# MedioPuente.net
KiCad netlist of a schematic drawn in Altium Designer
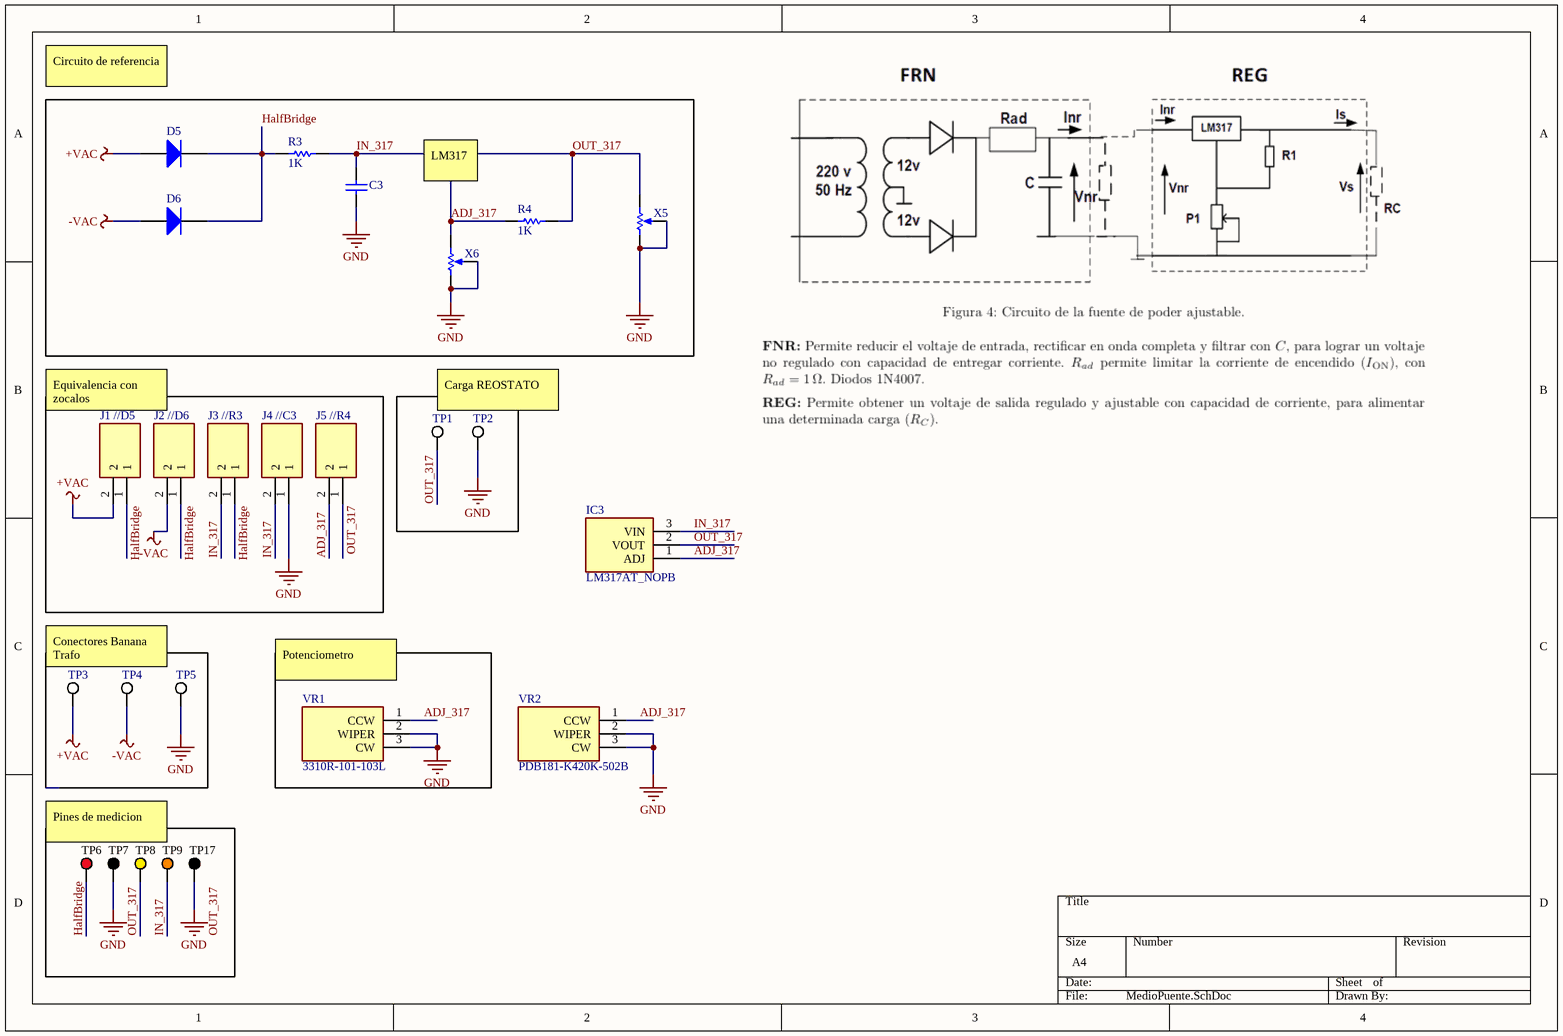
[diagram p0: MedioPuente.SchDoc]

(export (version "E")
  (design (tool "Eeschema 10.0.6"))
  (components
    (comp (ref "C3") (value "Capacitor") (libsource (lib "Simulation Generic Components") (part "Capacitor")))
    (comp (ref "D5") (value "Diode") (libsource (lib "Simulation Generic Components") (part "Diode")))
    (comp (ref "D6") (value "Diode") (libsource (lib "Simulation Generic Components") (part "Diode")))
    (comp (ref "IC3")
      (value "LM317AT_NOPB")
      (footprint "TO254P470X1028X1955-3P")
      (description "Integrated Circuit")
      (fields
        (field (name "MANUFACTURER_PART_NUMBER") "LM317AT/NOPB")
        (field (name "MOUSER PART NUMBER") "926-LM317AT/NOPB")
      )
      (libsource (lib "LM317") (part "LM317AT_NOPB"))
    )
    (comp (ref "J1")
      (value "D01-9970242")
      (footprint "D019970242")
      (description "IC Socket: 2 Pos Receptacle SIL Straight THT Strip")
      (fields (field (name "MOUSER PART NUMBER") "855-D01-9970242"))
      (libsource (lib "Zocalo_2pines") (part "D01-9970242"))
    )
    (comp (ref "J2")
      (value "D01-9970242")
      (footprint "D019970242")
      (description "IC Socket: 2 Pos Receptacle SIL Straight THT Strip")
      (fields (field (name "MOUSER PART NUMBER") "855-D01-9970242"))
      (libsource (lib "Zocalo_2pines") (part "D01-9970242"))
    )
    (comp (ref "J3")
      (value "D01-9970242")
      (footprint "D019970242")
      (description "IC Socket: 2 Pos Receptacle SIL Straight THT Strip")
      (fields (field (name "MOUSER PART NUMBER") "855-D01-9970242"))
      (libsource (lib "Zocalo_2pines") (part "D01-9970242"))
    )
    (comp (ref "J4")
      (value "D01-9970242")
      (footprint "D019970242")
      (description "IC Socket: 2 Pos Receptacle SIL Straight THT Strip")
      (fields (field (name "MOUSER PART NUMBER") "855-D01-9970242"))
      (libsource (lib "Zocalo_2pines") (part "D01-9970242"))
    )
    (comp (ref "J5")
      (value "D01-9970242")
      (footprint "D019970242")
      (description "IC Socket: 2 Pos Receptacle SIL Straight THT Strip")
      (fields (field (name "MOUSER PART NUMBER") "855-D01-9970242"))
      (libsource (lib "Zocalo_2pines") (part "D01-9970242"))
    )
    (comp (ref "R3")
      (value "1K")
      (description "Resistor")
      (libsource (lib "Simulation Generic Components") (part "Resistor"))
    )
    (comp (ref "R4")
      (value "1K")
      (description "Resistor")
      (libsource (lib "Simulation Generic Components") (part "Resistor"))
    )
    (comp (ref "TP1")
      (value "575-4")
      (footprint "KSTN-575-4")
      (description "Banana Jack, Non-Insulated, 1-Pin THD, RoHS, Bulk")
      (fields (field (name "MANUFACTURER") "Keystone-Electronics"))
      (libsource (lib "Altium Content Vault") (part "TESTPOINT_WHITE"))
    )
    (comp (ref "TP2")
      (value "575-4")
      (footprint "KSTN-575-4")
      (description "Banana Jack, Non-Insulated, 1-Pin THD, RoHS, Bulk")
      (fields (field (name "MANUFACTURER") "Keystone-Electronics"))
      (libsource (lib "Altium Content Vault") (part "TESTPOINT_WHITE"))
    )
    (comp (ref "TP3")
      (value "575-4")
      (footprint "KSTN-575-4")
      (description "Banana Jack, Non-Insulated, 1-Pin THD, RoHS, Bulk")
      (fields (field (name "MANUFACTURER") "Keystone-Electronics"))
      (libsource (lib "Altium Content Vault") (part "TESTPOINT_WHITE"))
    )
    (comp (ref "TP4")
      (value "575-4")
      (footprint "KSTN-575-4")
      (description "Banana Jack, Non-Insulated, 1-Pin THD, RoHS, Bulk")
      (fields (field (name "MANUFACTURER") "Keystone-Electronics"))
      (libsource (lib "Altium Content Vault") (part "TESTPOINT_WHITE"))
    )
    (comp (ref "TP5")
      (value "575-4")
      (footprint "KSTN-575-4")
      (description "Banana Jack, Non-Insulated, 1-Pin THD, RoHS, Bulk")
      (fields (field (name "MANUFACTURER") "Keystone-Electronics"))
      (libsource (lib "Altium Content Vault") (part "TESTPOINT_WHITE"))
    )
    (comp (ref "TP6")
      (value "5010")
      (footprint "KSTN-5010_V")
      (description "Test Point, Red, Through Hole, RoHS, Bulk")
      (fields (field (name "MANUFACTURER") "Keystone"))
      (libsource (lib "Altium Content Vault") (part "TESTPOINT_RED"))
    )
    (comp (ref "TP7")
      (value "5011")
      (footprint "KSTN-5011_V")
      (description "Test Point, Black, Through Hole, RoHS, Bulk")
      (fields (field (name "MANUFACTURER") "Keystone"))
      (libsource (lib "Altium Content Vault") (part "TESTPOINT_BLACK"))
    )
    (comp (ref "TP8")
      (value "5014")
      (footprint "KSTN-5014_V")
      (description "Test Point, Yellow, Through Hole, RoHS, Bulk")
      (fields (field (name "MANUFACTURER") "Keystone"))
      (libsource (lib "Altium Content Vault") (part "TESTPOINT_YELLOW"))
    )
    (comp (ref "TP9")
      (value "5013")
      (footprint "KSTN-5013_V")
      (description "Test Point, Orange, Through Hole, RoHS, Bulk")
      (fields (field (name "MANUFACTURER") "Keystone"))
      (libsource (lib "Altium Content Vault") (part "TESTPOINT_ORANGE"))
    )
    (comp (ref "TP17")
      (value "5011")
      (footprint "KSTN-5011_V")
      (description "Test Point, Black, Through Hole, RoHS, Bulk")
      (fields (field (name "MANUFACTURER") "Keystone"))
      (libsource (lib "Altium Content Vault") (part "TESTPOINT_BLACK"))
    )
    (comp (ref "VR1")
      (value "3310R-101-103L")
      (footprint "3310R125103L")
      (description "Variable Resistor")
      (fields (field (name "MOUSER PART NUMBER") "652-3310R-101-103L"))
      (libsource (lib "Potenciometro") (part "3310R-101-103L"))
    )
    (comp (ref "VR2")
      (value "PDB181-K420K-502B")
      (footprint "Potenciometro5K:PDB181K220K104B")
      (description "Variable Resistor")
      (fields (field (name "MOUSER PART NUMBER") "652-PDB181-K420K502B"))
      (libsource (lib "Potenciometro5K") (part "PDB181-K420K-502B"))
    )
    (comp (ref "X5")
      (value "Potentiometer")
      (libsource (lib "Simulation Generic Components") (part "Potentiometer"))
    )
    (comp (ref "X6")
      (value "Potentiometer")
      (libsource (lib "Simulation Generic Components") (part "Potentiometer"))
    )
  )
  (nets
    (net (code "1") (name "+VAC") (class "Default")
      (node (ref "D5") (pin "1") (pinfunction "A_1") (pintype "passive"))
      (node (ref "J1") (pin "2") (pinfunction "2_2") (pintype "passive"))
      (node (ref "TP3") (pin "1") (pinfunction "1_1") (pintype "passive"))
    )
    (net (code "2") (name "-VAC") (class "Default")
      (node (ref "D6") (pin "1") (pinfunction "A_1") (pintype "passive"))
      (node (ref "J2") (pin "2") (pinfunction "2_2") (pintype "passive"))
      (node (ref "TP4") (pin "1") (pinfunction "1_1") (pintype "passive"))
    )
    (net (code "3") (name "/ADJ_317") (class "Default")
      (node (ref "IC3") (pin "1") (pinfunction "ADJ_1") (pintype "passive"))
      (node (ref "J5") (pin "2") (pinfunction "2_2") (pintype "passive"))
      (node (ref "R4") (pin "1") (pinfunction "1_1") (pintype "passive"))
      (node (ref "VR1") (pin "1") (pinfunction "CCW_1") (pintype "passive"))
      (node (ref "VR2") (pin "1") (pinfunction "CCW_1") (pintype "passive"))
      (node (ref "X6") (pin "2") (pinfunction "BOT_2") (pintype "passive"))
    )
    (net (code "4") (name "/HalfBridge") (class "Default")
      (node (ref "D5") (pin "2") (pinfunction "K_2") (pintype "passive"))
      (node (ref "D6") (pin "2") (pinfunction "K_2") (pintype "passive"))
      (node (ref "J1") (pin "1") (pinfunction "1_1") (pintype "passive"))
      (node (ref "J2") (pin "1") (pinfunction "1_1") (pintype "passive"))
      (node (ref "J3") (pin "1") (pinfunction "1_1") (pintype "passive"))
      (node (ref "R3") (pin "1") (pinfunction "1_1") (pintype "passive"))
      (node (ref "TP6") (pin "1") (pinfunction "1_1") (pintype "passive"))
    )
    (net (code "5") (name "/IN_317") (class "Default")
      (node (ref "C3") (pin "2") (pinfunction "2_2") (pintype "passive"))
      (node (ref "IC3") (pin "3") (pinfunction "VIN_3") (pintype "passive"))
      (node (ref "J3") (pin "2") (pinfunction "2_2") (pintype "passive"))
      (node (ref "J4") (pin "2") (pinfunction "2_2") (pintype "passive"))
      (node (ref "R3") (pin "2") (pinfunction "2_2") (pintype "passive"))
      (node (ref "TP9") (pin "1") (pinfunction "1_1") (pintype "passive"))
    )
    (net (code "6") (name "/OUT_317") (class "Default")
      (node (ref "IC3") (pin "2") (pinfunction "VOUT_2") (pintype "passive"))
      (node (ref "J5") (pin "1") (pinfunction "1_1") (pintype "passive"))
      (node (ref "R4") (pin "2") (pinfunction "2_2") (pintype "passive"))
      (node (ref "TP1") (pin "1") (pinfunction "1_1") (pintype "passive"))
      (node (ref "TP8") (pin "1") (pinfunction "1_1") (pintype "passive"))
      (node (ref "X5") (pin "2") (pinfunction "BOT_2") (pintype "passive"))
    )
    (net (code "7") (name "GND") (class "Default")
      (node (ref "C3") (pin "1") (pinfunction "1_1") (pintype "passive"))
      (node (ref "J4") (pin "1") (pinfunction "1_1") (pintype "passive"))
      (node (ref "TP17") (pin "1") (pinfunction "1_1") (pintype "passive"))
      (node (ref "TP2") (pin "1") (pinfunction "1_1") (pintype "passive"))
      (node (ref "TP5") (pin "1") (pinfunction "1_1") (pintype "passive"))
      (node (ref "TP7") (pin "1") (pinfunction "1_1") (pintype "passive"))
      (node (ref "VR1") (pin "2") (pinfunction "WIPER_2") (pintype "passive"))
      (node (ref "VR1") (pin "3") (pinfunction "CW_3") (pintype "passive"))
      (node (ref "VR2") (pin "2") (pinfunction "WIPER_2") (pintype "passive"))
      (node (ref "VR2") (pin "3") (pinfunction "CW_3") (pintype "passive"))
      (node (ref "X5") (pin "1") (pinfunction "TOP_1") (pintype "passive"))
      (node (ref "X5") (pin "3") (pinfunction "TAP_3") (pintype "passive"))
      (node (ref "X6") (pin "1") (pinfunction "TOP_1") (pintype "passive"))
      (node (ref "X6") (pin "3") (pinfunction "TAP_3") (pintype "passive"))
    )
  )
)
